# vvm-visitorcounter.net
KiCad netlist of a schematic drawn in EAGLE
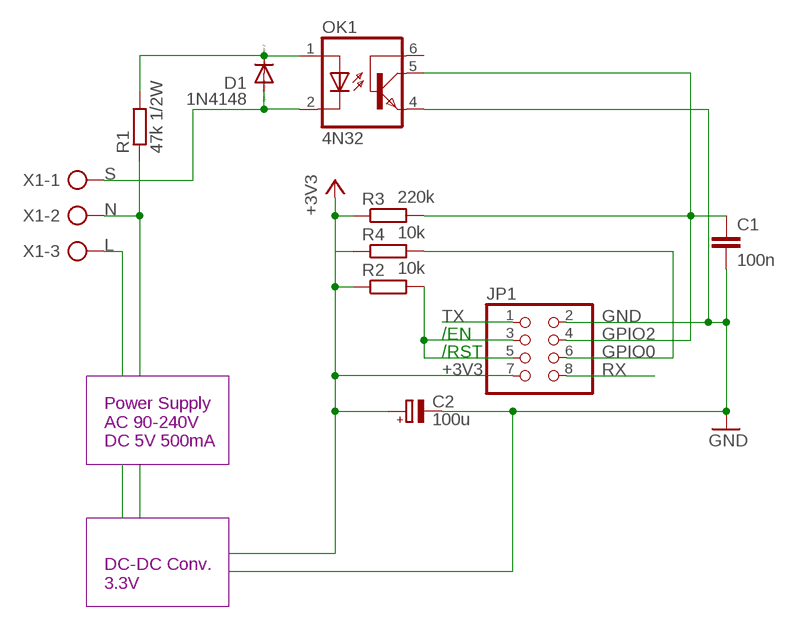
[diagram p0: schematic, sheet 1]

(export (version "E")
  (design (tool "Eeschema 10.0.6"))
  (components
    (comp (ref "C1")
      (value "100n")
      (footprint "eagle-import:C050-025X075")
      (libsource (lib "eagle-import") (part "C-EU050-025X075"))
    )
    (comp (ref "C2")
      (value "100u")
      (footprint "eagle-import:E2-5")
      (libsource (lib "eagle-import") (part "CPOL-EUE2-5"))
    )
    (comp (ref "D1")
      (value "1N4148")
      (footprint "eagle-import:DO35-7")
      (libsource (lib "eagle-import") (part "1N4148DO35-7"))
    )
    (comp (ref "JP1")
      (value "PINHD-2X4")
      (footprint "eagle-import:2X04")
      (libsource (lib "eagle-import") (part "PINHD-2X4"))
    )
    (comp (ref "OK1")
      (value "4N32")
      (footprint "eagle-import:DIL06")
      (fields (field (name "MPN") "4N25-M"))
      (libsource (lib "eagle-import") (part "4N?M25"))
    )
    (comp (ref "R1")
      (value "47k 1/2W")
      (footprint "eagle-import:0207_10")
      (libsource (lib "eagle-import") (part "R-EU_0207/10"))
    )
    (comp (ref "R2")
      (value "10k")
      (footprint "eagle-import:0207_10")
      (libsource (lib "eagle-import") (part "R-EU_0207/10"))
    )
    (comp (ref "R3")
      (value "220k")
      (footprint "eagle-import:0207_10")
      (libsource (lib "eagle-import") (part "R-EU_0207/10"))
    )
    (comp (ref "R4")
      (value "10k")
      (footprint "eagle-import:0207_10")
      (libsource (lib "eagle-import") (part "R-EU_0207/10"))
    )
    (comp (ref "X1")
      (value "AK300/3")
      (footprint "eagle-import:AK300_3")
      (libsource (lib "eagle-import") (part "AK300/3"))
    )
  )
  (nets
    (net (code "1") (name "+3V3") (class "Default")
      (node (ref "C2") (pin "+") (pinfunction "+_+") (pintype "passive"))
      (node (ref "JP1") (pin "7") (pinfunction "7_7") (pintype "passive"))
      (node (ref "R2") (pin "1") (pinfunction "1_1") (pintype "passive"))
      (node (ref "R3") (pin "1") (pinfunction "1_1") (pintype "passive"))
      (node (ref "R4") (pin "1") (pinfunction "1_1") (pintype "passive"))
    )
    (net (code "2") (name "/GPIO0") (class "Default")
      (node (ref "JP1") (pin "6") (pinfunction "6_6") (pintype "passive"))
      (node (ref "R4") (pin "2") (pinfunction "2_2") (pintype "passive"))
    )
    (net (code "3") (name "/GPIO2") (class "Default")
      (node (ref "C1") (pin "1") (pinfunction "1_1") (pintype "passive"))
      (node (ref "JP1") (pin "4") (pinfunction "4_4") (pintype "passive"))
      (node (ref "OK1") (pin "5") (pinfunction "COL_5") (pintype "passive"))
      (node (ref "R3") (pin "2") (pinfunction "2_2") (pintype "passive"))
    )
    (net (code "4") (name "/L") (class "Default")
      (node (ref "X1") (pin "3") (pinfunction "KL_3") (pintype "passive"))
    )
    (net (code "5") (name "/N") (class "Default")
      (node (ref "R1") (pin "1") (pinfunction "1_1") (pintype "passive"))
      (node (ref "X1") (pin "2") (pinfunction "KL_2") (pintype "passive"))
    )
    (net (code "6") (name "/RX") (class "Default")
      (node (ref "JP1") (pin "8") (pinfunction "8_8") (pintype "passive"))
    )
    (net (code "7") (name "/S") (class "Default")
      (node (ref "D1") (pin "A") (pinfunction "A_A") (pintype "passive"))
      (node (ref "OK1") (pin "2") (pinfunction "C_2") (pintype "passive"))
      (node (ref "X1") (pin "1") (pinfunction "KL_1") (pintype "passive"))
    )
    (net (code "8") (name "/TX") (class "Default")
      (node (ref "JP1") (pin "1") (pinfunction "1_1") (pintype "passive"))
    )
    (net (code "9") (name "GND") (class "Default")
      (node (ref "C1") (pin "2") (pinfunction "2_2") (pintype "passive"))
      (node (ref "C2") (pin "-") (pinfunction "-_-") (pintype "passive"))
      (node (ref "JP1") (pin "2") (pinfunction "2_2") (pintype "passive"))
      (node (ref "OK1") (pin "4") (pinfunction "EMI_4") (pintype "passive"))
    )
    (net (code "10") (name "Net-(JP1-Pad3)") (class "Default")
      (node (ref "JP1") (pin "3") (pinfunction "3_3") (pintype "passive"))
      (node (ref "JP1") (pin "5") (pinfunction "5_5") (pintype "passive"))
      (node (ref "R2") (pin "2") (pinfunction "2_2") (pintype "passive"))
    )
    (net (code "11") (name "Net-(OK1-A)") (class "Default")
      (node (ref "D1") (pin "C") (pinfunction "C_C") (pintype "passive"))
      (node (ref "OK1") (pin "1") (pinfunction "A_1") (pintype "passive"))
      (node (ref "R1") (pin "2") (pinfunction "2_2") (pintype "passive"))
    )
    (net (code "12") (name "unconnected-(OK1-BAS-Pad6)") (class "Default")
      (node (ref "OK1") (pin "6") (pinfunction "BAS_6") (pintype "passive"))
    )
  )
)
